# Y9A-07-1517.net
KiCad netlist of a schematic drawn in Altium Designer
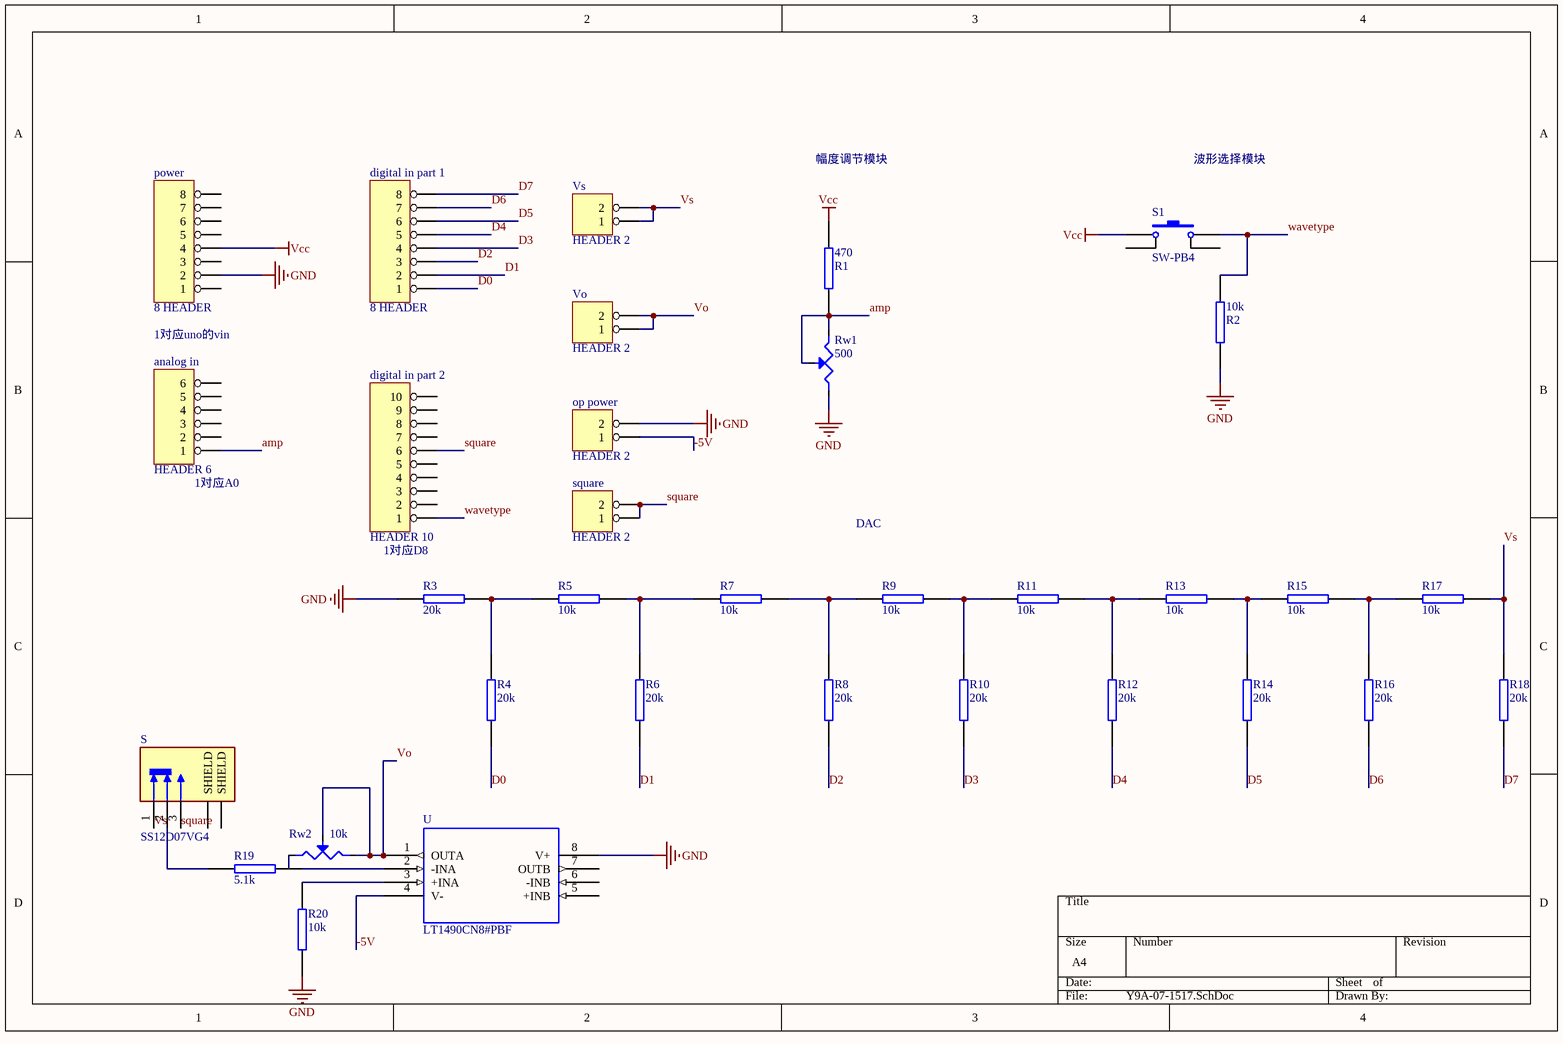
[diagram p0: Y9A-07-1517.SchDoc]

(export (version "E")
  (design (tool "Eeschema 10.0.6"))
  (components
    (comp (ref "10k")
      (value "R2")
      (footprint "AXIAL-0.4")
      (libsource (lib "Miscellaneous Devices") (part "RES2"))
    )
    (comp (ref "470")
      (value "R1")
      (footprint "AXIAL-0.4")
      (libsource (lib "Miscellaneous Devices") (part "RES2"))
    )
    (comp (ref "analog in")
      (value "HEADER 6")
      (footprint "SIP6")
      (libsource (lib "Miscellaneous Devices") (part "HEADER 6"))
    )
    (comp (ref "digital in part 1")
      (value "8 HEADER")
      (footprint "SIP8")
      (description "8 Pin Header")
      (libsource (lib "Miscellaneous Devices") (part "8 HEADER"))
    )
    (comp (ref "digital in part 2")
      (value "HEADER 10")
      (footprint "SIP10")
      (libsource (lib "Miscellaneous Devices") (part "HEADER 10"))
    )
    (comp (ref "op power")
      (value "HEADER 2")
      (footprint "POWER PLUG2")
      (libsource (lib "Miscellaneous Devices") (part "HEADER 2"))
    )
    (comp (ref "power")
      (value "8 HEADER")
      (footprint "SIP8")
      (description "8 Pin Header")
      (libsource (lib "Miscellaneous Devices") (part "8 HEADER"))
    )
    (comp (ref "R3")
      (value "20k")
      (footprint "AXIAL-0.4")
      (libsource (lib "Miscellaneous Devices") (part "RES2"))
    )
    (comp (ref "R4")
      (value "20k")
      (footprint "AXIAL-0.4")
      (libsource (lib "Miscellaneous Devices") (part "RES2"))
    )
    (comp (ref "R5")
      (value "10k")
      (footprint "AXIAL-0.4")
      (libsource (lib "Miscellaneous Devices") (part "RES2"))
    )
    (comp (ref "R6")
      (value "20k")
      (footprint "AXIAL-0.4")
      (libsource (lib "Miscellaneous Devices") (part "RES2"))
    )
    (comp (ref "R7")
      (value "10k")
      (footprint "AXIAL-0.4")
      (libsource (lib "Miscellaneous Devices") (part "RES2"))
    )
    (comp (ref "R8")
      (value "20k")
      (footprint "AXIAL-0.4")
      (libsource (lib "Miscellaneous Devices") (part "RES2"))
    )
    (comp (ref "R9")
      (value "10k")
      (footprint "AXIAL-0.4")
      (libsource (lib "Miscellaneous Devices") (part "RES2"))
    )
    (comp (ref "R10")
      (value "20k")
      (footprint "AXIAL-0.4")
      (libsource (lib "Miscellaneous Devices") (part "RES2"))
    )
    (comp (ref "R11")
      (value "10k")
      (footprint "AXIAL-0.4")
      (libsource (lib "Miscellaneous Devices") (part "RES2"))
    )
    (comp (ref "R12")
      (value "20k")
      (footprint "AXIAL-0.4")
      (libsource (lib "Miscellaneous Devices") (part "RES2"))
    )
    (comp (ref "R13")
      (value "10k")
      (footprint "AXIAL-0.4")
      (libsource (lib "Miscellaneous Devices") (part "RES2"))
    )
    (comp (ref "R14")
      (value "20k")
      (footprint "AXIAL-0.4")
      (libsource (lib "Miscellaneous Devices") (part "RES2"))
    )
    (comp (ref "R15")
      (value "10k")
      (footprint "AXIAL-0.4")
      (libsource (lib "Miscellaneous Devices") (part "RES2"))
    )
    (comp (ref "R16")
      (value "20k")
      (footprint "AXIAL-0.4")
      (libsource (lib "Miscellaneous Devices") (part "RES2"))
    )
    (comp (ref "R17")
      (value "10k")
      (footprint "AXIAL-0.4")
      (libsource (lib "Miscellaneous Devices") (part "RES2"))
    )
    (comp (ref "R18")
      (value "20k")
      (footprint "AXIAL-0.4")
      (libsource (lib "Miscellaneous Devices") (part "RES2"))
    )
    (comp (ref "R19")
      (value "5.1k")
      (footprint "AXIAL-0.4")
      (libsource (lib "Miscellaneous Devices") (part "RES2"))
    )
    (comp (ref "R20")
      (value "10k")
      (footprint "AXIAL-0.4")
      (libsource (lib "Miscellaneous Devices") (part "RES2"))
    )
    (comp (ref "Rw1")
      (value "500")
      (footprint "VR5")
      (description "Potentiometer")
      (libsource (lib "Miscellaneous Devices") (part "POT1"))
    )
    (comp (ref "Rw2")
      (value "10k")
      (footprint "VR5")
      (description "Potentiometer")
      (libsource (lib "Miscellaneous Devices") (part "POT1"))
    )
    (comp (ref "S")
      (value "SS12D07VG4")
      (footprint "SW_SS12D07VG4")
      (description "Switch Slide ON ON SPDT Top Slide 0.3A 30VDC PC Pins Bracket Mount/Through Hole Automotive Bulk")
      (fields (field (name "MF") "Shouhan"))
      (libsource (lib "SS12D07VG4") (part "SS12D07VG4"))
    )
    (comp (ref "S1")
      (value "SW-PB4")
      (footprint "AN-S")
      (description "微动开关")
      (fields (field (name "PUBLISHER") "Altium Limited"))
      (libsource (lib "fszhang") (part "SW-PB4"))
    )
    (comp (ref "square")
      (value "HEADER 2")
      (footprint "SIP-2")
      (libsource (lib "Miscellaneous Devices") (part "HEADER 2"))
    )
    (comp (ref "U")
      (value "LT1490CN8#PBF")
      (footprint "PDIP-8_N")
      (description "Standard (General Purpose) Amplifier 2 Circuit Rail-to-Rail 8-PDIP")
      (fields (field (name "MF") "Analog Devices"))
      (libsource (lib "LT1490CN8_PBF") (part "LT1490CN8#PBF"))
    )
    (comp (ref "Vo")
      (value "HEADER 2")
      (footprint "SIP-2")
      (libsource (lib "Miscellaneous Devices") (part "HEADER 2"))
    )
    (comp (ref "Vs")
      (value "HEADER 2")
      (footprint "SIP-2")
      (libsource (lib "Miscellaneous Devices") (part "HEADER 2"))
    )
  )
  (nets
    (net (code "1") (name "/-5V") (class "Default")
      (node (ref "U") (pin "4") (pinfunction "V-_4") (pintype "power_in"))
      (node (ref "op power") (pin "1") (pinfunction "1_1") (pintype "passive"))
    )
    (net (code "2") (name "/D0") (class "Default")
      (node (ref "R4") (pin "1") (pinfunction "1_1") (pintype "passive"))
      (node (ref "digital in part 1") (pin "1") (pinfunction "1_1") (pintype "passive"))
    )
    (net (code "3") (name "/D1") (class "Default")
      (node (ref "R6") (pin "1") (pinfunction "1_1") (pintype "passive"))
      (node (ref "digital in part 1") (pin "2") (pinfunction "2_2") (pintype "passive"))
    )
    (net (code "4") (name "/D2") (class "Default")
      (node (ref "R8") (pin "1") (pinfunction "1_1") (pintype "passive"))
      (node (ref "digital in part 1") (pin "3") (pinfunction "3_3") (pintype "passive"))
    )
    (net (code "5") (name "/D3") (class "Default")
      (node (ref "R10") (pin "1") (pinfunction "1_1") (pintype "passive"))
      (node (ref "digital in part 1") (pin "4") (pinfunction "4_4") (pintype "passive"))
    )
    (net (code "6") (name "/D4") (class "Default")
      (node (ref "R12") (pin "1") (pinfunction "1_1") (pintype "passive"))
      (node (ref "digital in part 1") (pin "5") (pinfunction "5_5") (pintype "passive"))
    )
    (net (code "7") (name "/D5") (class "Default")
      (node (ref "R14") (pin "1") (pinfunction "1_1") (pintype "passive"))
      (node (ref "digital in part 1") (pin "6") (pinfunction "6_6") (pintype "passive"))
    )
    (net (code "8") (name "/D6") (class "Default")
      (node (ref "R16") (pin "1") (pinfunction "1_1") (pintype "passive"))
      (node (ref "digital in part 1") (pin "7") (pinfunction "7_7") (pintype "passive"))
    )
    (net (code "9") (name "/D7") (class "Default")
      (node (ref "R18") (pin "1") (pinfunction "1_1") (pintype "passive"))
      (node (ref "digital in part 1") (pin "8") (pinfunction "8_8") (pintype "passive"))
    )
    (net (code "10") (name "/Vo") (class "Default")
      (node (ref "Rw2") (pin "2") (pinfunction "2_2") (pintype "passive"))
      (node (ref "Rw2") (pin "3") (pinfunction "W_3") (pintype "passive"))
      (node (ref "U") (pin "1") (pinfunction "OUTA_1") (pintype "output"))
      (node (ref "Vo") (pin "1") (pinfunction "1_1") (pintype "passive"))
      (node (ref "Vo") (pin "2") (pinfunction "2_2") (pintype "passive"))
    )
    (net (code "11") (name "/Vs") (class "Default")
      (node (ref "R17") (pin "2") (pinfunction "2_2") (pintype "passive"))
      (node (ref "R18") (pin "2") (pinfunction "2_2") (pintype "passive"))
      (node (ref "S") (pin "1") (pinfunction "1_1") (pintype "passive"))
      (node (ref "Vs") (pin "1") (pinfunction "1_1") (pintype "passive"))
      (node (ref "Vs") (pin "2") (pinfunction "2_2") (pintype "passive"))
    )
    (net (code "12") (name "/amp") (class "Default")
      (node (ref "470") (pin "1") (pinfunction "1_1") (pintype "passive"))
      (node (ref "Rw1") (pin "2") (pinfunction "2_2") (pintype "passive"))
      (node (ref "Rw1") (pin "3") (pinfunction "W_3") (pintype "passive"))
      (node (ref "analog in") (pin "1") (pinfunction "1_1") (pintype "passive"))
    )
    (net (code "13") (name "/square") (class "Default")
      (node (ref "S") (pin "3") (pinfunction "3_3") (pintype "passive"))
      (node (ref "digital in part 2") (pin "6") (pinfunction "6_6") (pintype "passive"))
      (node (ref "square") (pin "1") (pinfunction "1_1") (pintype "passive"))
      (node (ref "square") (pin "2") (pinfunction "2_2") (pintype "passive"))
    )
    (net (code "14") (name "/wavetype") (class "Default")
      (node (ref "10k") (pin "2") (pinfunction "2_2") (pintype "passive"))
      (node (ref "S1") (pin "2") (pinfunction "2_2") (pintype "passive"))
      (node (ref "digital in part 2") (pin "1") (pinfunction "1_1") (pintype "passive"))
    )
    (net (code "15") (name "GND") (class "Default")
      (node (ref "10k") (pin "1") (pinfunction "1_1") (pintype "passive"))
      (node (ref "R20") (pin "1") (pinfunction "1_1") (pintype "passive"))
      (node (ref "R3") (pin "1") (pinfunction "1_1") (pintype "passive"))
      (node (ref "Rw1") (pin "1") (pinfunction "1_1") (pintype "passive"))
      (node (ref "U") (pin "8") (pinfunction "V+_8") (pintype "power_in"))
      (node (ref "op power") (pin "2") (pinfunction "2_2") (pintype "passive"))
      (node (ref "power") (pin "2") (pinfunction "2_2") (pintype "passive"))
    )
    (net (code "16") (name "Net-(R3-Pad2)") (class "Default")
      (node (ref "R3") (pin "2") (pinfunction "2_2") (pintype "passive"))
      (node (ref "R4") (pin "2") (pinfunction "2_2") (pintype "passive"))
      (node (ref "R5") (pin "1") (pinfunction "1_1") (pintype "passive"))
    )
    (net (code "17") (name "Net-(R5-Pad2)") (class "Default")
      (node (ref "R5") (pin "2") (pinfunction "2_2") (pintype "passive"))
      (node (ref "R6") (pin "2") (pinfunction "2_2") (pintype "passive"))
      (node (ref "R7") (pin "1") (pinfunction "1_1") (pintype "passive"))
    )
    (net (code "18") (name "Net-(R7-Pad2)") (class "Default")
      (node (ref "R7") (pin "2") (pinfunction "2_2") (pintype "passive"))
      (node (ref "R8") (pin "2") (pinfunction "2_2") (pintype "passive"))
      (node (ref "R9") (pin "1") (pinfunction "1_1") (pintype "passive"))
    )
    (net (code "19") (name "Net-(R10-Pad2)") (class "Default")
      (node (ref "R10") (pin "2") (pinfunction "2_2") (pintype "passive"))
      (node (ref "R11") (pin "1") (pinfunction "1_1") (pintype "passive"))
      (node (ref "R9") (pin "2") (pinfunction "2_2") (pintype "passive"))
    )
    (net (code "20") (name "Net-(R11-Pad2)") (class "Default")
      (node (ref "R11") (pin "2") (pinfunction "2_2") (pintype "passive"))
      (node (ref "R12") (pin "2") (pinfunction "2_2") (pintype "passive"))
      (node (ref "R13") (pin "1") (pinfunction "1_1") (pintype "passive"))
    )
    (net (code "21") (name "Net-(R13-Pad2)") (class "Default")
      (node (ref "R13") (pin "2") (pinfunction "2_2") (pintype "passive"))
      (node (ref "R14") (pin "2") (pinfunction "2_2") (pintype "passive"))
      (node (ref "R15") (pin "1") (pinfunction "1_1") (pintype "passive"))
    )
    (net (code "22") (name "Net-(R15-Pad2)") (class "Default")
      (node (ref "R15") (pin "2") (pinfunction "2_2") (pintype "passive"))
      (node (ref "R16") (pin "2") (pinfunction "2_2") (pintype "passive"))
      (node (ref "R17") (pin "1") (pinfunction "1_1") (pintype "passive"))
    )
    (net (code "23") (name "Net-(R19-Pad1)") (class "Default")
      (node (ref "R19") (pin "1") (pinfunction "1_1") (pintype "passive"))
      (node (ref "S") (pin "2") (pinfunction "2_2") (pintype "passive"))
    )
    (net (code "24") (name "Net-(U-+INA)") (class "Default")
      (node (ref "R20") (pin "2") (pinfunction "2_2") (pintype "passive"))
      (node (ref "U") (pin "3") (pinfunction "+INA_3") (pintype "input"))
    )
    (net (code "25") (name "Net-(U--INA)") (class "Default")
      (node (ref "R19") (pin "2") (pinfunction "2_2") (pintype "passive"))
      (node (ref "U") (pin "2") (pinfunction "-INA_2") (pintype "input"))
    )
    (net (code "26") (name "Vcc") (class "Default")
      (node (ref "470") (pin "2") (pinfunction "2_2") (pintype "passive"))
      (node (ref "S1") (pin "1") (pinfunction "1_1") (pintype "passive"))
      (node (ref "power") (pin "4") (pinfunction "4_4") (pintype "passive"))
    )
    (net (code "27") (name "unconnected-(Rw2-Pad1)") (class "Default")
      (node (ref "Rw2") (pin "1") (pinfunction "1_1") (pintype "passive"))
    )
    (net (code "28") (name "unconnected-(S-SHIELD-PadS1)") (class "Default")
      (node (ref "S") (pin "S1") (pinfunction "SHIELD_S1") (pintype "passive"))
    )
    (net (code "29") (name "unconnected-(S-SHIELD-PadS2)") (class "Default")
      (node (ref "S") (pin "S2") (pinfunction "SHIELD_S2") (pintype "passive"))
    )
    (net (code "30") (name "unconnected-(S1-Pad3)") (class "Default")
      (node (ref "S1") (pin "3") (pinfunction "3_3") (pintype "passive"))
    )
    (net (code "31") (name "unconnected-(S1-Pad4)") (class "Default")
      (node (ref "S1") (pin "4") (pinfunction "4_4") (pintype "passive"))
    )
    (net (code "32") (name "unconnected-(U-+INB-Pad5)") (class "Default")
      (node (ref "U") (pin "5") (pinfunction "+INB_5") (pintype "input"))
    )
    (net (code "33") (name "unconnected-(U--INB-Pad6)") (class "Default")
      (node (ref "U") (pin "6") (pinfunction "-INB_6") (pintype "input"))
    )
    (net (code "34") (name "unconnected-(U-OUTB-Pad7)") (class "Default")
      (node (ref "U") (pin "7") (pinfunction "OUTB_7") (pintype "output"))
    )
    (net (code "35") (name "unconnected-(analog in-Pad2)") (class "Default")
      (node (ref "analog in") (pin "2") (pinfunction "2_2") (pintype "passive"))
    )
    (net (code "36") (name "unconnected-(analog in-Pad3)") (class "Default")
      (node (ref "analog in") (pin "3") (pinfunction "3_3") (pintype "passive"))
    )
    (net (code "37") (name "unconnected-(analog in-Pad4)") (class "Default")
      (node (ref "analog in") (pin "4") (pinfunction "4_4") (pintype "passive"))
    )
    (net (code "38") (name "unconnected-(analog in-Pad5)") (class "Default")
      (node (ref "analog in") (pin "5") (pinfunction "5_5") (pintype "passive"))
    )
    (net (code "39") (name "unconnected-(analog in-Pad6)") (class "Default")
      (node (ref "analog in") (pin "6") (pinfunction "6_6") (pintype "passive"))
    )
    (net (code "40") (name "unconnected-(digital in part 2-Pad2)") (class "Default")
      (node (ref "digital in part 2") (pin "2") (pinfunction "2_2") (pintype "passive"))
    )
    (net (code "41") (name "unconnected-(digital in part 2-Pad3)") (class "Default")
      (node (ref "digital in part 2") (pin "3") (pinfunction "3_3") (pintype "passive"))
    )
    (net (code "42") (name "unconnected-(digital in part 2-Pad4)") (class "Default")
      (node (ref "digital in part 2") (pin "4") (pinfunction "4_4") (pintype "passive"))
    )
    (net (code "43") (name "unconnected-(digital in part 2-Pad5)") (class "Default")
      (node (ref "digital in part 2") (pin "5") (pinfunction "5_5") (pintype "passive"))
    )
    (net (code "44") (name "unconnected-(digital in part 2-Pad7)") (class "Default")
      (node (ref "digital in part 2") (pin "7") (pinfunction "7_7") (pintype "passive"))
    )
    (net (code "45") (name "unconnected-(digital in part 2-Pad8)") (class "Default")
      (node (ref "digital in part 2") (pin "8") (pinfunction "8_8") (pintype "passive"))
    )
    (net (code "46") (name "unconnected-(digital in part 2-Pad9)") (class "Default")
      (node (ref "digital in part 2") (pin "9") (pinfunction "9_9") (pintype "passive"))
    )
    (net (code "47") (name "unconnected-(digital in part 2-Pad10)") (class "Default")
      (node (ref "digital in part 2") (pin "10") (pinfunction "10_10") (pintype "passive"))
    )
    (net (code "48") (name "unconnected-(power-Pad1)") (class "Default")
      (node (ref "power") (pin "1") (pinfunction "1_1") (pintype "passive"))
    )
    (net (code "49") (name "unconnected-(power-Pad3)") (class "Default")
      (node (ref "power") (pin "3") (pinfunction "3_3") (pintype "passive"))
    )
    (net (code "50") (name "unconnected-(power-Pad5)") (class "Default")
      (node (ref "power") (pin "5") (pinfunction "5_5") (pintype "passive"))
    )
    (net (code "51") (name "unconnected-(power-Pad6)") (class "Default")
      (node (ref "power") (pin "6") (pinfunction "6_6") (pintype "passive"))
    )
    (net (code "52") (name "unconnected-(power-Pad7)") (class "Default")
      (node (ref "power") (pin "7") (pinfunction "7_7") (pintype "passive"))
    )
    (net (code "53") (name "unconnected-(power-Pad8)") (class "Default")
      (node (ref "power") (pin "8") (pinfunction "8_8") (pintype "passive"))
    )
  )
)
